# Power_Control.net
KiCad netlist of a schematic drawn in Altium Designer
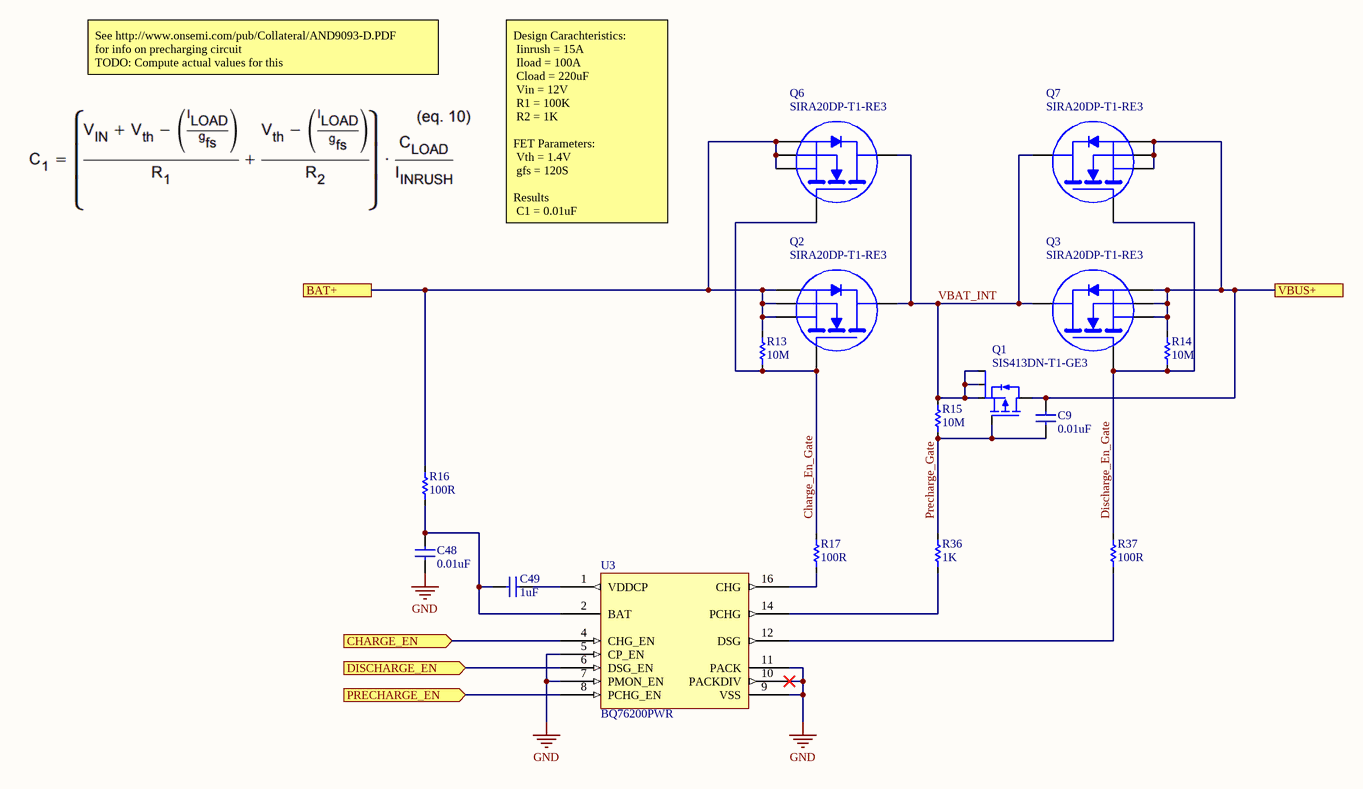
[diagram p0: Power_Control.SchDoc]

(export (version "E")
  (design (tool "Eeschema 10.0.6"))
  (components
    (comp (ref "C9")
      (value "0.01uF")
      (footprint "0402_CAPACITOR")
      (description "CAP CERM 0.01uF 10% 50V 0402")
      (fields (field (name "VOLTAGE") "50V") (field (name "Comment") "CAP 0.01uF 50V X7R"))
      (libsource (lib "capacitor") (part "C_0402_0.01uF_50V_10%"))
    )
    (comp (ref "C48")
      (value "0.01uF")
      (footprint "0402_CAPACITOR")
      (description "CAP CERM 0.01uF 10% 50V 0402")
      (fields (field (name "VOLTAGE") "50V") (field (name "Comment") "CAP 0.01uF 50V X7R"))
      (libsource (lib "capacitor") (part "C_0402_0.01uF_50V_10%"))
    )
    (comp (ref "C49")
      (value "1uF")
      (footprint "1206_CAPACITOR")
      (description "CAP CERM 1uF 20% 25V 1206")
      (fields
        (field (name "VOLTAGE") "25V")
        (field (name "Comment") "CAP 1uF 25V X7R")
        (field (name "SVP CREATOR") "Spencer Berglund")
      )
      (libsource (lib "capacitor") (part "C_1206_1uF_25V_20%"))
    )
    (comp (ref "Q1")
      (value "SIS413DN-T1-GE3")
      (footprint "PowerPAK-1212-8")
      (description "P-Channel 30V 18A (Tc) 3.7W (Ta), 52W (Tc) Surface Mount PowerPAK® 1212-8")
      (fields (field (name "MANUFACTURER") "Vishay Siliconix"))
      (libsource (lib "transistor") (part "Q_SIS413DN-T1-GE3"))
    )
    (comp (ref "Q2")
      (value "SIRA20DP-T1-RE3")
      (footprint "PowerPAK-SO-8")
      (description "N-Channel 25V 81.7A (Ta), 100A (Tc) 6.25W (Ta), 104W (Tc) Surface Mount PowerPAK® SO-8")
      (fields (field (name "MANUFACTURER") "Vishay"))
      (libsource (lib "transistor") (part "Q_SIRA20DP-T1-RE3"))
    )
    (comp (ref "Q3")
      (value "SIRA20DP-T1-RE3")
      (footprint "PowerPAK-SO-8")
      (description "N-Channel 25V 81.7A (Ta), 100A (Tc) 6.25W (Ta), 104W (Tc) Surface Mount PowerPAK® SO-8")
      (fields (field (name "MANUFACTURER") "Vishay"))
      (libsource (lib "transistor") (part "Q_SIRA20DP-T1-RE3"))
    )
    (comp (ref "Q6")
      (value "SIRA20DP-T1-RE3")
      (footprint "PowerPAK-SO-8")
      (description "N-Channel 25V 81.7A (Ta), 100A (Tc) 6.25W (Ta), 104W (Tc) Surface Mount PowerPAK® SO-8")
      (fields (field (name "MANUFACTURER") "Vishay"))
      (libsource (lib "transistor") (part "Q_SIRA20DP-T1-RE3"))
    )
    (comp (ref "Q7")
      (value "SIRA20DP-T1-RE3")
      (footprint "PowerPAK-SO-8")
      (description "N-Channel 25V 81.7A (Ta), 100A (Tc) 6.25W (Ta), 104W (Tc) Surface Mount PowerPAK® SO-8")
      (fields (field (name "MANUFACTURER") "Vishay"))
      (libsource (lib "transistor") (part "Q_SIRA20DP-T1-RE3"))
    )
    (comp (ref "R13")
      (value "10M")
      (footprint "0402_Resistor")
      (description "Generic 0402 Resistor (10.2R to 10M)")
      (fields (field (name "TOLERANCE") "±1%") (field (name "MANUFACTURER") "Yageo"))
      (libsource (lib "resistor") (part "R_0402_generic_1%"))
    )
    (comp (ref "R14")
      (value "10M")
      (footprint "0402_Resistor")
      (description "Generic 0402 Resistor (10.2R to 10M)")
      (fields (field (name "TOLERANCE") "±1%") (field (name "MANUFACTURER") "Yageo"))
      (libsource (lib "resistor") (part "R_0402_generic_1%"))
    )
    (comp (ref "R15")
      (value "10M")
      (footprint "0402_Resistor")
      (description "Generic 0402 Resistor (10.2R to 10M)")
      (fields (field (name "TOLERANCE") "±1%") (field (name "MANUFACTURER") "Yageo"))
      (libsource (lib "resistor") (part "R_0402_generic_1%"))
    )
    (comp (ref "R16")
      (value "100R")
      (footprint "0402_Resistor")
      (description "Generic 0402 Resistor (10.2R to 10M)")
      (fields (field (name "TOLERANCE") "±1%") (field (name "MANUFACTURER") "Yageo"))
      (libsource (lib "resistor") (part "R_0402_generic_1%"))
    )
    (comp (ref "R17")
      (value "100R")
      (footprint "0402_Resistor")
      (description "Generic 0402 Resistor (10.2R to 10M)")
      (fields (field (name "TOLERANCE") "±1%") (field (name "MANUFACTURER") "Yageo"))
      (libsource (lib "resistor") (part "R_0402_generic_1%"))
    )
    (comp (ref "R36")
      (value "1K")
      (footprint "0402_Resistor")
      (description "Generic 0402 Resistor (10.2R to 10M)")
      (fields (field (name "TOLERANCE") "±1%") (field (name "MANUFACTURER") "Yageo"))
      (libsource (lib "resistor") (part "R_0402_generic_1%"))
    )
    (comp (ref "R37")
      (value "100R")
      (footprint "0402_Resistor")
      (description "Generic 0402 Resistor (10.2R to 10M)")
      (fields (field (name "TOLERANCE") "±1%") (field (name "MANUFACTURER") "Yageo"))
      (libsource (lib "resistor") (part "R_0402_generic_1%"))
    )
    (comp (ref "U3")
      (value "BQ76200PWR")
      (footprint "TSSOP-16")
      (description "Battery Battery Protection IC Lead Acid 16-TSSOP")
      (libsource (lib "ic") (part "U_BQ76200PWR"))
    )
  )
  (nets
    (net (code "1") (name "/BAT+") (class "Default")
      (node (ref "Q2") (pin "1") (pinfunction "SOURCE_1") (pintype "passive"))
      (node (ref "Q2") (pin "2") (pinfunction "SOURCE_2") (pintype "passive"))
      (node (ref "Q2") (pin "3") (pinfunction "SOURCE_3") (pintype "passive"))
      (node (ref "Q6") (pin "1") (pinfunction "SOURCE_1") (pintype "passive"))
      (node (ref "Q6") (pin "2") (pinfunction "SOURCE_2") (pintype "passive"))
      (node (ref "Q6") (pin "3") (pinfunction "SOURCE_3") (pintype "passive"))
      (node (ref "R13") (pin "2") (pinfunction "2_2") (pintype "passive"))
      (node (ref "R16") (pin "2") (pinfunction "2_2") (pintype "passive"))
    )
    (net (code "2") (name "/CHARGE_EN") (class "Default")
      (node (ref "U3") (pin "4") (pinfunction "CHG_EN_4") (pintype "input"))
    )
    (net (code "3") (name "/Charge_En_Gate") (class "Default")
      (node (ref "Q2") (pin "4") (pinfunction "GATE_4") (pintype "passive"))
      (node (ref "Q6") (pin "4") (pinfunction "GATE_4") (pintype "passive"))
      (node (ref "R13") (pin "1") (pinfunction "1_1") (pintype "passive"))
      (node (ref "R17") (pin "2") (pinfunction "2_2") (pintype "passive"))
    )
    (net (code "4") (name "/DISCHARGE_EN") (class "Default")
      (node (ref "U3") (pin "6") (pinfunction "DSG_EN_6") (pintype "input"))
    )
    (net (code "5") (name "/Discharge_En_Gate") (class "Default")
      (node (ref "Q3") (pin "4") (pinfunction "GATE_4") (pintype "passive"))
      (node (ref "Q7") (pin "4") (pinfunction "GATE_4") (pintype "passive"))
      (node (ref "R14") (pin "1") (pinfunction "1_1") (pintype "passive"))
      (node (ref "R37") (pin "2") (pinfunction "2_2") (pintype "passive"))
    )
    (net (code "6") (name "/PRECHARGE_EN") (class "Default")
      (node (ref "U3") (pin "8") (pinfunction "PCHG_EN_8") (pintype "input"))
    )
    (net (code "7") (name "/Precharge_Gate") (class "Default")
      (node (ref "C9") (pin "2") (pinfunction "2_2") (pintype "passive"))
      (node (ref "Q1") (pin "4") (pinfunction "GATE_4") (pintype "passive"))
      (node (ref "R15") (pin "1") (pinfunction "1_1") (pintype "passive"))
      (node (ref "R36") (pin "2") (pinfunction "2_2") (pintype "passive"))
    )
    (net (code "8") (name "/VBAT_INT") (class "Default")
      (node (ref "Q1") (pin "1") (pinfunction "SOURCE_1") (pintype "passive"))
      (node (ref "Q1") (pin "2") (pinfunction "SOURCE_2") (pintype "passive"))
      (node (ref "Q1") (pin "3") (pinfunction "SOURCE_3") (pintype "passive"))
      (node (ref "Q2") (pin "5") (pinfunction "DRAIN_5") (pintype "passive"))
      (node (ref "Q3") (pin "5") (pinfunction "DRAIN_5") (pintype "passive"))
      (node (ref "Q6") (pin "5") (pinfunction "DRAIN_5") (pintype "passive"))
      (node (ref "Q7") (pin "5") (pinfunction "DRAIN_5") (pintype "passive"))
      (node (ref "R15") (pin "2") (pinfunction "2_2") (pintype "passive"))
    )
    (net (code "9") (name "/VBUS+") (class "Default")
      (node (ref "C9") (pin "1") (pinfunction "1_1") (pintype "passive"))
      (node (ref "Q1") (pin "5") (pinfunction "DRAIN_5") (pintype "passive"))
      (node (ref "Q3") (pin "1") (pinfunction "SOURCE_1") (pintype "passive"))
      (node (ref "Q3") (pin "2") (pinfunction "SOURCE_2") (pintype "passive"))
      (node (ref "Q3") (pin "3") (pinfunction "SOURCE_3") (pintype "passive"))
      (node (ref "Q7") (pin "1") (pinfunction "SOURCE_1") (pintype "passive"))
      (node (ref "Q7") (pin "2") (pinfunction "SOURCE_2") (pintype "passive"))
      (node (ref "Q7") (pin "3") (pinfunction "SOURCE_3") (pintype "passive"))
      (node (ref "R14") (pin "2") (pinfunction "2_2") (pintype "passive"))
    )
    (net (code "10") (name "GND") (class "Default")
      (node (ref "C48") (pin "2") (pinfunction "2_2") (pintype "passive"))
      (node (ref "U3") (pin "10") (pinfunction "PACKDIV_10") (pintype "output"))
      (node (ref "U3") (pin "11") (pinfunction "PACK_11") (pintype "power_in"))
      (node (ref "U3") (pin "5") (pinfunction "CP_EN_5") (pintype "input"))
      (node (ref "U3") (pin "7") (pinfunction "PMON_EN_7") (pintype "input"))
      (node (ref "U3") (pin "9") (pinfunction "VSS_9") (pintype "power_in"))
    )
    (net (code "11") (name "Net-(U3-BAT)") (class "Default")
      (node (ref "C48") (pin "1") (pinfunction "1_1") (pintype "passive"))
      (node (ref "C49") (pin "1") (pinfunction "1_1") (pintype "passive"))
      (node (ref "R16") (pin "1") (pinfunction "1_1") (pintype "passive"))
      (node (ref "U3") (pin "2") (pinfunction "BAT_2") (pintype "power_in"))
    )
    (net (code "12") (name "Net-(U3-CHG)") (class "Default")
      (node (ref "R17") (pin "1") (pinfunction "1_1") (pintype "passive"))
      (node (ref "U3") (pin "16") (pinfunction "CHG_16") (pintype "output"))
    )
    (net (code "13") (name "Net-(U3-DSG)") (class "Default")
      (node (ref "R37") (pin "1") (pinfunction "1_1") (pintype "passive"))
      (node (ref "U3") (pin "12") (pinfunction "DSG_12") (pintype "output"))
    )
    (net (code "14") (name "Net-(U3-PCHG)") (class "Default")
      (node (ref "R36") (pin "1") (pinfunction "1_1") (pintype "passive"))
      (node (ref "U3") (pin "14") (pinfunction "PCHG_14") (pintype "output"))
    )
    (net (code "15") (name "Net-(U3-VDDCP)") (class "Default")
      (node (ref "C49") (pin "2") (pinfunction "2_2") (pintype "passive"))
      (node (ref "U3") (pin "1") (pinfunction "VDDCP_1") (pintype "output"))
    )
  )
)
